# brd1refsheet.net
KiCad netlist of a schematic drawn in Altium Designer
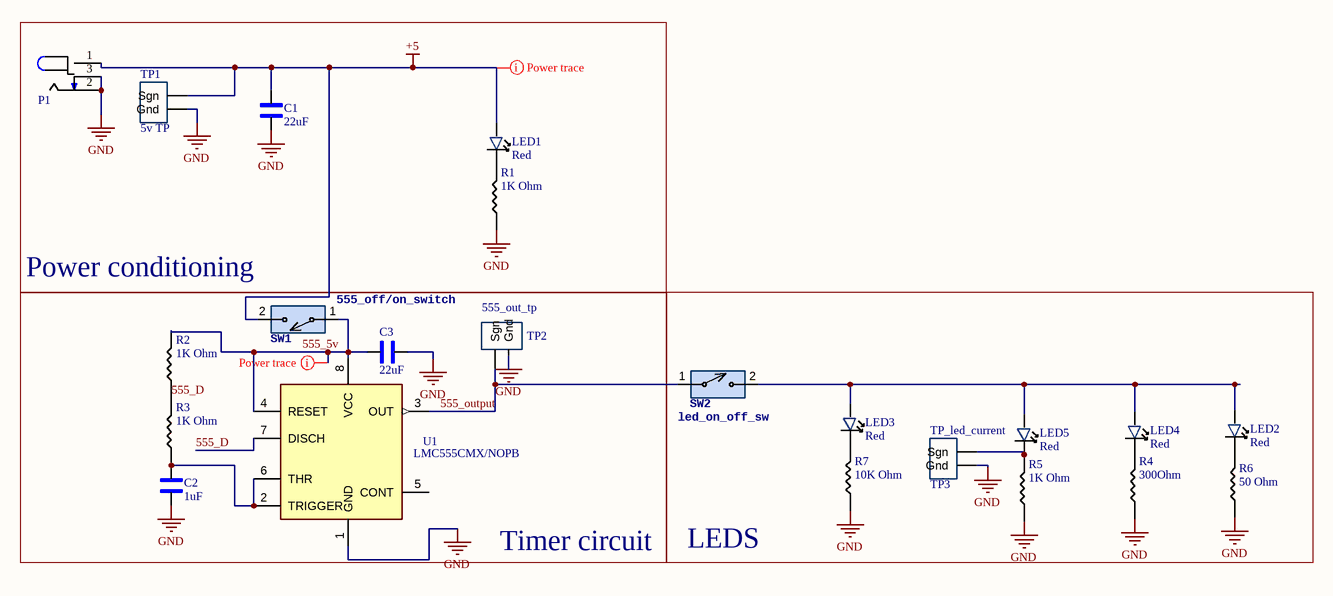
[diagram p0: brd1refsheet.SchDoc]

(export (version "E")
  (design (tool "Eeschema 10.0.6"))
  (components
    (comp (ref "C1")
      (value "22uF")
      (footprint "1206_Passive_Capacitor")
      (description "22uF ±10% 25V X5R 1206 Multilayer Ceramic Capacitors MLCC - SMD/SMT RoHS")
      (fields (field (name "MFR PART #") "CL31A226KAHNNNE") (field (name "LCSC PART#") "C12891"))
      (libsource (lib "ECEN5730Lib_2023_05_DS") (part "C_22uF_1206"))
    )
    (comp (ref "C2")
      (value "1uF")
      (footprint "1206_Passive_Capacitor")
      (description "MULTILAYER CERAMIC CAPACITORS MLCC - SMD/SMT 1UF 50V 1206 ROHS")
      (fields (field (name "MFR PART #") "CL31B105KBHNNNE") (field (name "LCSC PART#") "C1848"))
      (libsource (lib "ECEN5730Lib_2023_05_DS") (part "C_1uF_1206"))
    )
    (comp (ref "C3")
      (value "22uF")
      (footprint "1206_Passive_Capacitor")
      (description "22uF ±10% 25V X5R 1206 Multilayer Ceramic Capacitors MLCC - SMD/SMT RoHS")
      (fields (field (name "MFR PART #") "CL31A226KAHNNNE") (field (name "LCSC PART#") "C12891"))
      (libsource (lib "ECEN5730Lib_2023_05_DS") (part "C_22uF_1206"))
    )
    (comp (ref "LED1")
      (value "Red")
      (footprint "LED_1206")
      (description "Red 621~631nm 1206 Light Emitting Diodes (LED) RoHS")
      (fields (field (name "MFR PART #") "15-21/R6C-FQ1R1B/2T") (field (name "LCSC PART#") "C93133"))
      (libsource (lib "ECEN5730Lib_2023_05_DS") (part "LED_RED_1206"))
    )
    (comp (ref "LED2")
      (value "Red")
      (footprint "LED_1206")
      (description "Red 621~631nm 1206 Light Emitting Diodes (LED) RoHS")
      (fields (field (name "MFR PART #") "15-21/R6C-FQ1R1B/2T") (field (name "LCSC PART#") "C93133"))
      (libsource (lib "ECEN5730Lib_2023_05_DS") (part "LED_RED_1206"))
    )
    (comp (ref "LED3")
      (value "Red")
      (footprint "LED_1206")
      (description "Red 621~631nm 1206 Light Emitting Diodes (LED) RoHS")
      (fields (field (name "MFR PART #") "15-21/R6C-FQ1R1B/2T") (field (name "LCSC PART#") "C93133"))
      (libsource (lib "ECEN5730Lib_2023_05_DS") (part "LED_RED_1206"))
    )
    (comp (ref "LED4")
      (value "Red")
      (footprint "LED_1206")
      (description "Red 621~631nm 1206 Light Emitting Diodes (LED) RoHS")
      (fields (field (name "MFR PART #") "15-21/R6C-FQ1R1B/2T") (field (name "LCSC PART#") "C93133"))
      (libsource (lib "ECEN5730Lib_2023_05_DS") (part "LED_RED_1206"))
    )
    (comp (ref "LED5")
      (value "Red")
      (footprint "LED_1206")
      (description "Red 621~631nm 1206 Light Emitting Diodes (LED) RoHS")
      (fields (field (name "MFR PART #") "15-21/R6C-FQ1R1B/2T") (field (name "LCSC PART#") "C93133"))
      (libsource (lib "ECEN5730Lib_2023_05_DS") (part "LED_RED_1206"))
    )
    (comp (ref "P1")
      (value "Power Jack")
      (footprint "Power_Jack")
      (description "Power Barrel Connector Jack 2.10mm ID (0.083\"), 5.50mm OD (0.217\") Through Hole, Right Angle")
      (fields (field (name "MFR PART #") "PJ-102A") (field (name "LCSC PART#") "C136744"))
      (libsource (lib "ECEN5730Lib_2023_05_DS") (part "P_Power Jack"))
    )
    (comp (ref "R1")
      (value "1K Ohm")
      (footprint "1206_Passive_Resitor")
      (description "CHIP RESISTOR - SURFACE MOUNT 1KOHMS ±1% 1/4W 1206 ROHS")
      (fields (field (name "MFR PART #") "RNCP1206FTD1K00CT") (field (name "LCSC PART#") "C4410"))
      (libsource (lib "ECEN5730Lib_2023_05_DS") (part "R_1K_1206"))
    )
    (comp (ref "R2")
      (value "1K Ohm")
      (footprint "1206_Passive_Resitor")
      (description "CHIP RESISTOR - SURFACE MOUNT 1KOHMS ±1% 1/4W 1206 ROHS")
      (fields (field (name "MFR PART #") "RNCP1206FTD1K00CT") (field (name "LCSC PART#") "C4410"))
      (libsource (lib "ECEN5730Lib_2023_05_DS") (part "R_1K_1206"))
    )
    (comp (ref "R3")
      (value "1K Ohm")
      (footprint "1206_Passive_Resitor")
      (description "CHIP RESISTOR - SURFACE MOUNT 1KOHMS ±1% 1/4W 1206 ROHS")
      (fields (field (name "MFR PART #") "RNCP1206FTD1K00CT") (field (name "LCSC PART#") "C4410"))
      (libsource (lib "ECEN5730Lib_2023_05_DS") (part "R_1K_1206"))
    )
    (comp (ref "R4")
      (value "300Ohm")
      (footprint "1206_Passive_Resitor")
      (description "CHIP RESISTOR - SURFACE MOUNT 300OHMS ±1% 1/4W 1206 ROHS")
      (fields (field (name "MFR PART #") "1206W4F3000T5E") (field (name "LCSC PART#") "C17887"))
      (libsource (lib "ECEN5730Lib_2023_05_DS") (part "R_300Ohm_1206"))
    )
    (comp (ref "R5")
      (value "1K Ohm")
      (footprint "1206_Passive_Resitor")
      (description "CHIP RESISTOR - SURFACE MOUNT 1KOHMS ±1% 1/4W 1206 ROHS")
      (fields (field (name "MFR PART #") "RNCP1206FTD1K00CT") (field (name "LCSC PART#") "C4410"))
      (libsource (lib "ECEN5730Lib_2023_05_DS") (part "R_1K_1206"))
    )
    (comp (ref "R6")
      (value "50 Ohm")
      (footprint "1206_Passive_Resitor")
      (description "CHIP RESISTOR - SURFACE MOUNT 100MOHMS ±1% 1/4W 1206 ROHS")
      (fields (field (name "MFR PART #") "1206W4F1006T5E") (field (name "LCSC PART#") "C59781"))
      (libsource (lib "ECEN5730Lib_2023_05_DS") (part "R_100M_1206_1"))
    )
    (comp (ref "R7")
      (value "10K Ohm")
      (footprint "1206_Passive_Resitor")
      (description "CHIP RESISTOR - SURFACE MOUNT 100MOHMS ±1% 1/4W 1206 ROHS")
      (fields (field (name "MFR PART #") "1206W4F1006T5E") (field (name "LCSC PART#") "C59781"))
      (libsource (lib "ECEN5730Lib_2023_05_DS") (part "R_100M_1206_1"))
    )
    (comp (ref "SW1")
      (value "555_off/on_switch")
      (footprint "2Pin-Header-Conn")
      (description "2Pin Header")
      (fields (field (name "LCSC PART#") "C124375"))
      (libsource (lib "ECEN5730Lib_2023_05_DS") (part "SW_2Pin_100mil_Switch"))
    )
    (comp (ref "SW2")
      (value "led_on_off_sw")
      (footprint "2Pin-Header-Conn")
      (description "2Pin Header")
      (fields (field (name "LCSC PART#") "C124375"))
      (libsource (lib "") (part "SW_2Pin_100mil_Switch_1"))
    )
    (comp (ref "TP1")
      (value "5v TP")
      (footprint "TP10x_Probe")
      (description "Test Point 300 mil centers")
      (libsource (lib "") (part "TP_10x_Probe_1"))
    )
    (comp (ref "TP2")
      (value "555_out_tp")
      (footprint "TP10x_Probe")
      (description "Test Point 300 mil centers")
      (libsource (lib "ECEN5730Lib_2023_05_DS") (part "TP_10x_Probe"))
    )
    (comp (ref "TP3")
      (value "TP_led_current")
      (footprint "TP10x_Probe")
      (description "Test Point 300 mil centers")
      (libsource (lib "") (part "TP_10x_Probe_1"))
    )
    (comp (ref "U1")
      (value "LMC555CMX/NOPB")
      (footprint "TS555IDTTR")
      (description "555 Type, Timer/Oscillator _Single_ IC 3MHz 8-SO")
      (fields (field (name "LCSC PART#") "C90760"))
      (libsource (lib "ECEN5730Lib_2023_05_DS") (part "U_555_Fast"))
    )
  )
  (nets
    (net (code "1") (name "+5") (class "Default")
      (node (ref "C1") (pin "2") (pinfunction "2_2") (pintype "passive"))
      (node (ref "LED1") (pin "1") (pinfunction "1_1") (pintype "passive"))
      (node (ref "P1") (pin "1") (pinfunction "1_1") (pintype "power_in"))
      (node (ref "SW1") (pin "2") (pinfunction "2_2") (pintype "passive"))
      (node (ref "TP1") (pin "1") (pinfunction "Sgn_1") (pintype "passive"))
    )
    (net (code "2") (name "/555_5v") (class "Default")
      (node (ref "C3") (pin "1") (pinfunction "1_1") (pintype "passive"))
      (node (ref "R2") (pin "2") (pinfunction "2_2") (pintype "passive"))
      (node (ref "SW1") (pin "1") (pinfunction "1_1") (pintype "passive"))
      (node (ref "U1") (pin "4") (pinfunction "RESET_4") (pintype "passive"))
      (node (ref "U1") (pin "8") (pinfunction "VCC_8") (pintype "power_in"))
    )
    (net (code "3") (name "/555_D") (class "Default")
      (node (ref "R2") (pin "1") (pinfunction "1_1") (pintype "passive"))
      (node (ref "R3") (pin "2") (pinfunction "2_2") (pintype "passive"))
      (node (ref "U1") (pin "7") (pinfunction "DISCH_7") (pintype "passive"))
    )
    (net (code "4") (name "/555_output") (class "Default")
      (node (ref "SW2") (pin "1") (pinfunction "1_1") (pintype "passive"))
      (node (ref "TP2") (pin "1") (pinfunction "Sgn_1") (pintype "passive"))
      (node (ref "U1") (pin "3") (pinfunction "OUT_3") (pintype "output"))
    )
    (net (code "5") (name "GND") (class "Default")
      (node (ref "C1") (pin "1") (pinfunction "1_1") (pintype "passive"))
      (node (ref "C2") (pin "1") (pinfunction "1_1") (pintype "passive"))
      (node (ref "C3") (pin "2") (pinfunction "2_2") (pintype "passive"))
      (node (ref "P1") (pin "2") (pinfunction "2_2") (pintype "power_in"))
      (node (ref "P1") (pin "3") (pinfunction "3_3") (pintype "power_in"))
      (node (ref "R1") (pin "1") (pinfunction "1_1") (pintype "passive"))
      (node (ref "R4") (pin "1") (pinfunction "1_1") (pintype "passive"))
      (node (ref "R5") (pin "1") (pinfunction "1_1") (pintype "passive"))
      (node (ref "R6") (pin "1") (pinfunction "1_1") (pintype "passive"))
      (node (ref "R7") (pin "1") (pinfunction "1_1") (pintype "passive"))
      (node (ref "TP1") (pin "2") (pinfunction "Gnd_2") (pintype "passive"))
      (node (ref "TP2") (pin "2") (pinfunction "Gnd_2") (pintype "passive"))
      (node (ref "TP3") (pin "2") (pinfunction "Gnd_2") (pintype "passive"))
      (node (ref "U1") (pin "1") (pinfunction "GND_1") (pintype "power_in"))
    )
    (net (code "6") (name "Net-(LED1-Pad2)") (class "Default")
      (node (ref "LED1") (pin "2") (pinfunction "2_2") (pintype "passive"))
      (node (ref "R1") (pin "2") (pinfunction "2_2") (pintype "passive"))
    )
    (net (code "7") (name "Net-(LED2-Pad1)") (class "Default")
      (node (ref "LED2") (pin "1") (pinfunction "1_1") (pintype "passive"))
      (node (ref "LED3") (pin "1") (pinfunction "1_1") (pintype "passive"))
      (node (ref "LED4") (pin "1") (pinfunction "1_1") (pintype "passive"))
      (node (ref "LED5") (pin "1") (pinfunction "1_1") (pintype "passive"))
      (node (ref "SW2") (pin "2") (pinfunction "2_2") (pintype "passive"))
    )
    (net (code "8") (name "Net-(LED2-Pad2)") (class "Default")
      (node (ref "LED2") (pin "2") (pinfunction "2_2") (pintype "passive"))
      (node (ref "R6") (pin "2") (pinfunction "2_2") (pintype "passive"))
    )
    (net (code "9") (name "Net-(LED3-Pad2)") (class "Default")
      (node (ref "LED3") (pin "2") (pinfunction "2_2") (pintype "passive"))
      (node (ref "R7") (pin "2") (pinfunction "2_2") (pintype "passive"))
    )
    (net (code "10") (name "Net-(LED4-Pad2)") (class "Default")
      (node (ref "LED4") (pin "2") (pinfunction "2_2") (pintype "passive"))
      (node (ref "R4") (pin "2") (pinfunction "2_2") (pintype "passive"))
    )
    (net (code "11") (name "Net-(TP3-Sgn)") (class "Default")
      (node (ref "LED5") (pin "2") (pinfunction "2_2") (pintype "passive"))
      (node (ref "R5") (pin "2") (pinfunction "2_2") (pintype "passive"))
      (node (ref "TP3") (pin "1") (pinfunction "Sgn_1") (pintype "passive"))
    )
    (net (code "12") (name "Net-(U1-THR)") (class "Default")
      (node (ref "C2") (pin "2") (pinfunction "2_2") (pintype "passive"))
      (node (ref "R3") (pin "1") (pinfunction "1_1") (pintype "passive"))
      (node (ref "U1") (pin "2") (pinfunction "TRIGGER_2") (pintype "passive"))
      (node (ref "U1") (pin "6") (pinfunction "THR_6") (pintype "passive"))
    )
    (net (code "13") (name "unconnected-(U1-CONT-Pad5)") (class "Default")
      (node (ref "U1") (pin "5") (pinfunction "CONT_5") (pintype "passive"))
    )
  )
)
